# Fan_Board.net
KiCad netlist of a schematic drawn in Altium Designer
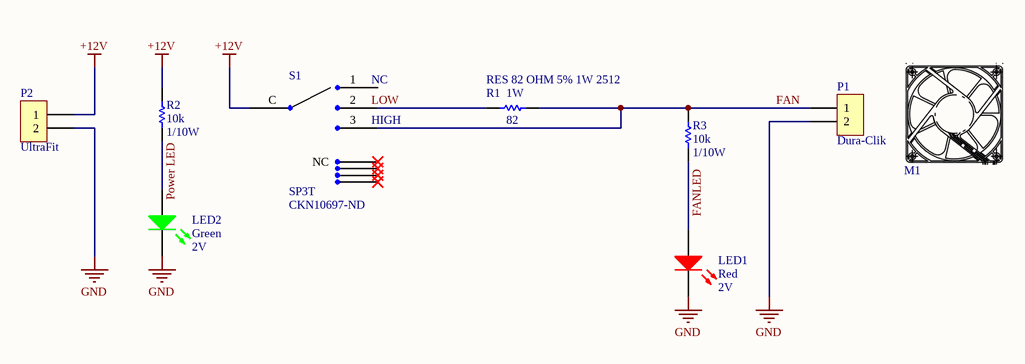
[diagram p0: Fan_Board.SchDoc]

(export (version "E")
  (design (tool "Eeschema 10.0.6"))
  (components
    (comp (ref "LED1")
      (value "LED RED CLEAR 2V 0603")
      (footprint "LED_0603")
      (description "Red 631nm LED Indication - Discrete 2V 0603 (1608 Metric)")
      (fields
        (field (name "MANUFACTURER") "Wurth Electronics Inc.")
        (field (name "MANUFACTURER PART NUMBER") "150060RS75000")
        (field (name "COLOR") "Red")
        (field (name "VOLTAGE - FORWARD (VF) (TYP)") "2V")
      )
      (libsource (lib "Schematic Diagrams") (part "LED RED CLEAR 2V 0603"))
    )
    (comp (ref "LED2")
      (value "LED GREEN CLEAR 2V 0603")
      (footprint "LED_0603")
      (description "Green 572nm LED Indication - Discrete 2V 0603 (1608 Metric)")
      (fields
        (field (name "MANUFACTURER") "Wurth Electronics Inc.")
        (field (name "MANUFACTURER PART NUMBER") "150060VS75000")
        (field (name "COLOR") "Green")
        (field (name "VOLTAGE - FORWARD (VF) (TYP)") "2V")
      )
      (libsource (lib "Schematic Diagrams") (part "LED GREEN CLEAR 2V 0603"))
    )
    (comp (ref "M1")
      (value "FAN 0.03A 12VDC")
      (description "FAN 0.03A 12VDC 2 WIRE")
      (fields
        (field (name "MANUFACTURER") "Sunon")
        (field (name "MANUFACTURER PART NUMBER") "HA40201V4-1000U-A99")
      )
      (libsource (lib "Schematic Diagrams") (part "FAN 0.03A 12VDC"))
    )
    (comp (ref "P1")
      (value "Dura-Clik")
      (footprint "CONN, 2POS Dura-Click Vertical")
      (description "2 Positions Header, Shrouded Connector 0.079\" (2.00mm) Surface Mount, Vertical Tin")
      (fields
        (field (name "MANUFACTURER") "Molex, LLC")
        (field (name "MANUFACTURER PART NUMBER") "5600200220")
      )
      (libsource (lib "Schematic Diagrams") (part "CONN 2POS DURA-CLIK 0.079{dblquote} VERT"))
    )
    (comp (ref "P2")
      (value "CONN 2POS ULTRA-FIT 0.138\"")
      (footprint "CONN, 2POS ULTRA-FIT")
      (description "2 Positions Header, Shrouded Connector 0.138\" (3.50mm) Through Hole Gold")
      (fields (field (name "VOLTAGE") "400V") (field (name "SERIES") "UltraFit"))
      (libsource (lib "Schematic Diagrams") (part "CONN 2POS ULTRA-FIT 0.138{dblquote}"))
    )
    (comp (ref "R1")
      (value "RES 82 OHM 5% 1W 2512")
      (footprint "RES2512")
      (fields
        (field (name "MANUFACTURER") "Panasonic")
        (field (name "MANUFACTURER PART NUMBER") "ERJ-P06J820V")
        (field (name "TOLERANCE") "5%")
      )
      (libsource (lib "Schematic Diagrams") (part "RES 82 OHM 5% 1W 2512"))
    )
    (comp (ref "R2")
      (value "RES 10K OHM 1% 1/10W 0603")
      (footprint "RES, 0603")
      (description "RES SMD 10K OHM 1% 1/10W 0603")
      (fields
        (field (name "TOLERANCE") "±1%")
        (field (name "RESISTANCE") "10k")
        (field (name "POWER") "1/10W")
      )
      (libsource (lib "Schematic Diagrams") (part "RES 10K OHM 1% 1/10W 0603"))
    )
    (comp (ref "R3")
      (value "RES 10K OHM 1% 1/10W 0603")
      (footprint "RES, 0603")
      (description "RES SMD 10K OHM 1% 1/10W 0603")
      (fields
        (field (name "TOLERANCE") "±1%")
        (field (name "RESISTANCE") "10k")
        (field (name "POWER") "1/10W")
      )
      (libsource (lib "Schematic Diagrams") (part "RES 10K OHM 1% 1/10W 0603"))
    )
    (comp (ref "S1")
      (value "SP3T")
      (footprint "SW ROT RM SERIES")
      (description "SWITCH ROTARY 3POS 500MA 24V")
      (fields
        (field (name "MANUFACTURER") "ITT C&K")
        (field (name "MANUFACTURER PART NUMBER") "RM103772BCB")
        (field (name "SUPPLIER PART NUMBER 1") "CKN10697-ND")
      )
      (libsource (lib "Schematic Diagrams") (part "SW ROT SP3T-NO 0.5A 24VDC"))
    )
  )
  (nets
    (net (code "1") (name "+12V") (class "Default")
      (node (ref "P2") (pin "1") (pinfunction "1_1") (pintype "passive"))
      (node (ref "R2") (pin "1") (pinfunction "1_1") (pintype "passive"))
      (node (ref "S1") (pin "C") (pinfunction "4_C") (pintype "passive"))
    )
    (net (code "2") (name "/FAN") (class "Default")
      (node (ref "P1") (pin "1") (pinfunction "1_1") (pintype "passive"))
      (node (ref "R1") (pin "1") (pinfunction "1_1") (pintype "passive"))
      (node (ref "R3") (pin "1") (pinfunction "1_1") (pintype "passive"))
      (node (ref "S1") (pin "3") (pinfunction "7_3") (pintype "passive"))
    )
    (net (code "3") (name "/FANLED") (class "Default")
      (node (ref "LED1") (pin "1") (pinfunction "A_1") (pintype "passive"))
      (node (ref "R3") (pin "2") (pinfunction "2_2") (pintype "passive"))
    )
    (net (code "5") (name "/Power LED") (class "Default")
      (node (ref "LED2") (pin "1") (pinfunction "A_1") (pintype "passive"))
      (node (ref "R2") (pin "2") (pinfunction "2_2") (pintype "passive"))
    )
    (net (code "6") (name "GND") (class "Default")
      (node (ref "LED1") (pin "2") (pinfunction "K_2") (pintype "passive"))
      (node (ref "LED2") (pin "2") (pinfunction "K_2") (pintype "passive"))
      (node (ref "P1") (pin "2") (pinfunction "2_2") (pintype "passive"))
      (node (ref "P2") (pin "2") (pinfunction "2_2") (pintype "passive"))
    )
    (net (code "7") (name "Net-(S1-6)") (class "Default")
      (node (ref "R1") (pin "2") (pinfunction "2_2") (pintype "passive"))
      (node (ref "S1") (pin "2") (pinfunction "6_2") (pintype "passive"))
    )
    (net (code "8") (name "unconnected-(S1-5-Pad1)") (class "Default")
      (node (ref "S1") (pin "1") (pinfunction "5_1") (pintype "passive"))
    )
    (net (code "9") (name "unconnected-(S1-PadNC)") (class "Default")
      (node (ref "S1") (pin "NC") (pinfunction "NC_NC") (pintype "passive+no_connect"))
    )
    (net (code "10") (name "unconnected-(S1-PadNC)_1") (class "Default")
      (node (ref "S1") (pin "NC") (pinfunction "NC_NC") (pintype "passive+no_connect"))
    )
    (net (code "11") (name "unconnected-(S1-PadNC)_2") (class "Default")
      (node (ref "S1") (pin "NC") (pinfunction "NC_NC") (pintype "passive+no_connect"))
    )
    (net (code "12") (name "unconnected-(S1-PadNC)_3") (class "Default")
      (node (ref "S1") (pin "NC") (pinfunction "NC_NC") (pintype "passive+no_connect"))
    )
  )
)
